# P-MT3620RDB-1-0_PIO.net
KiCad netlist of a schematic drawn in Altium Designer
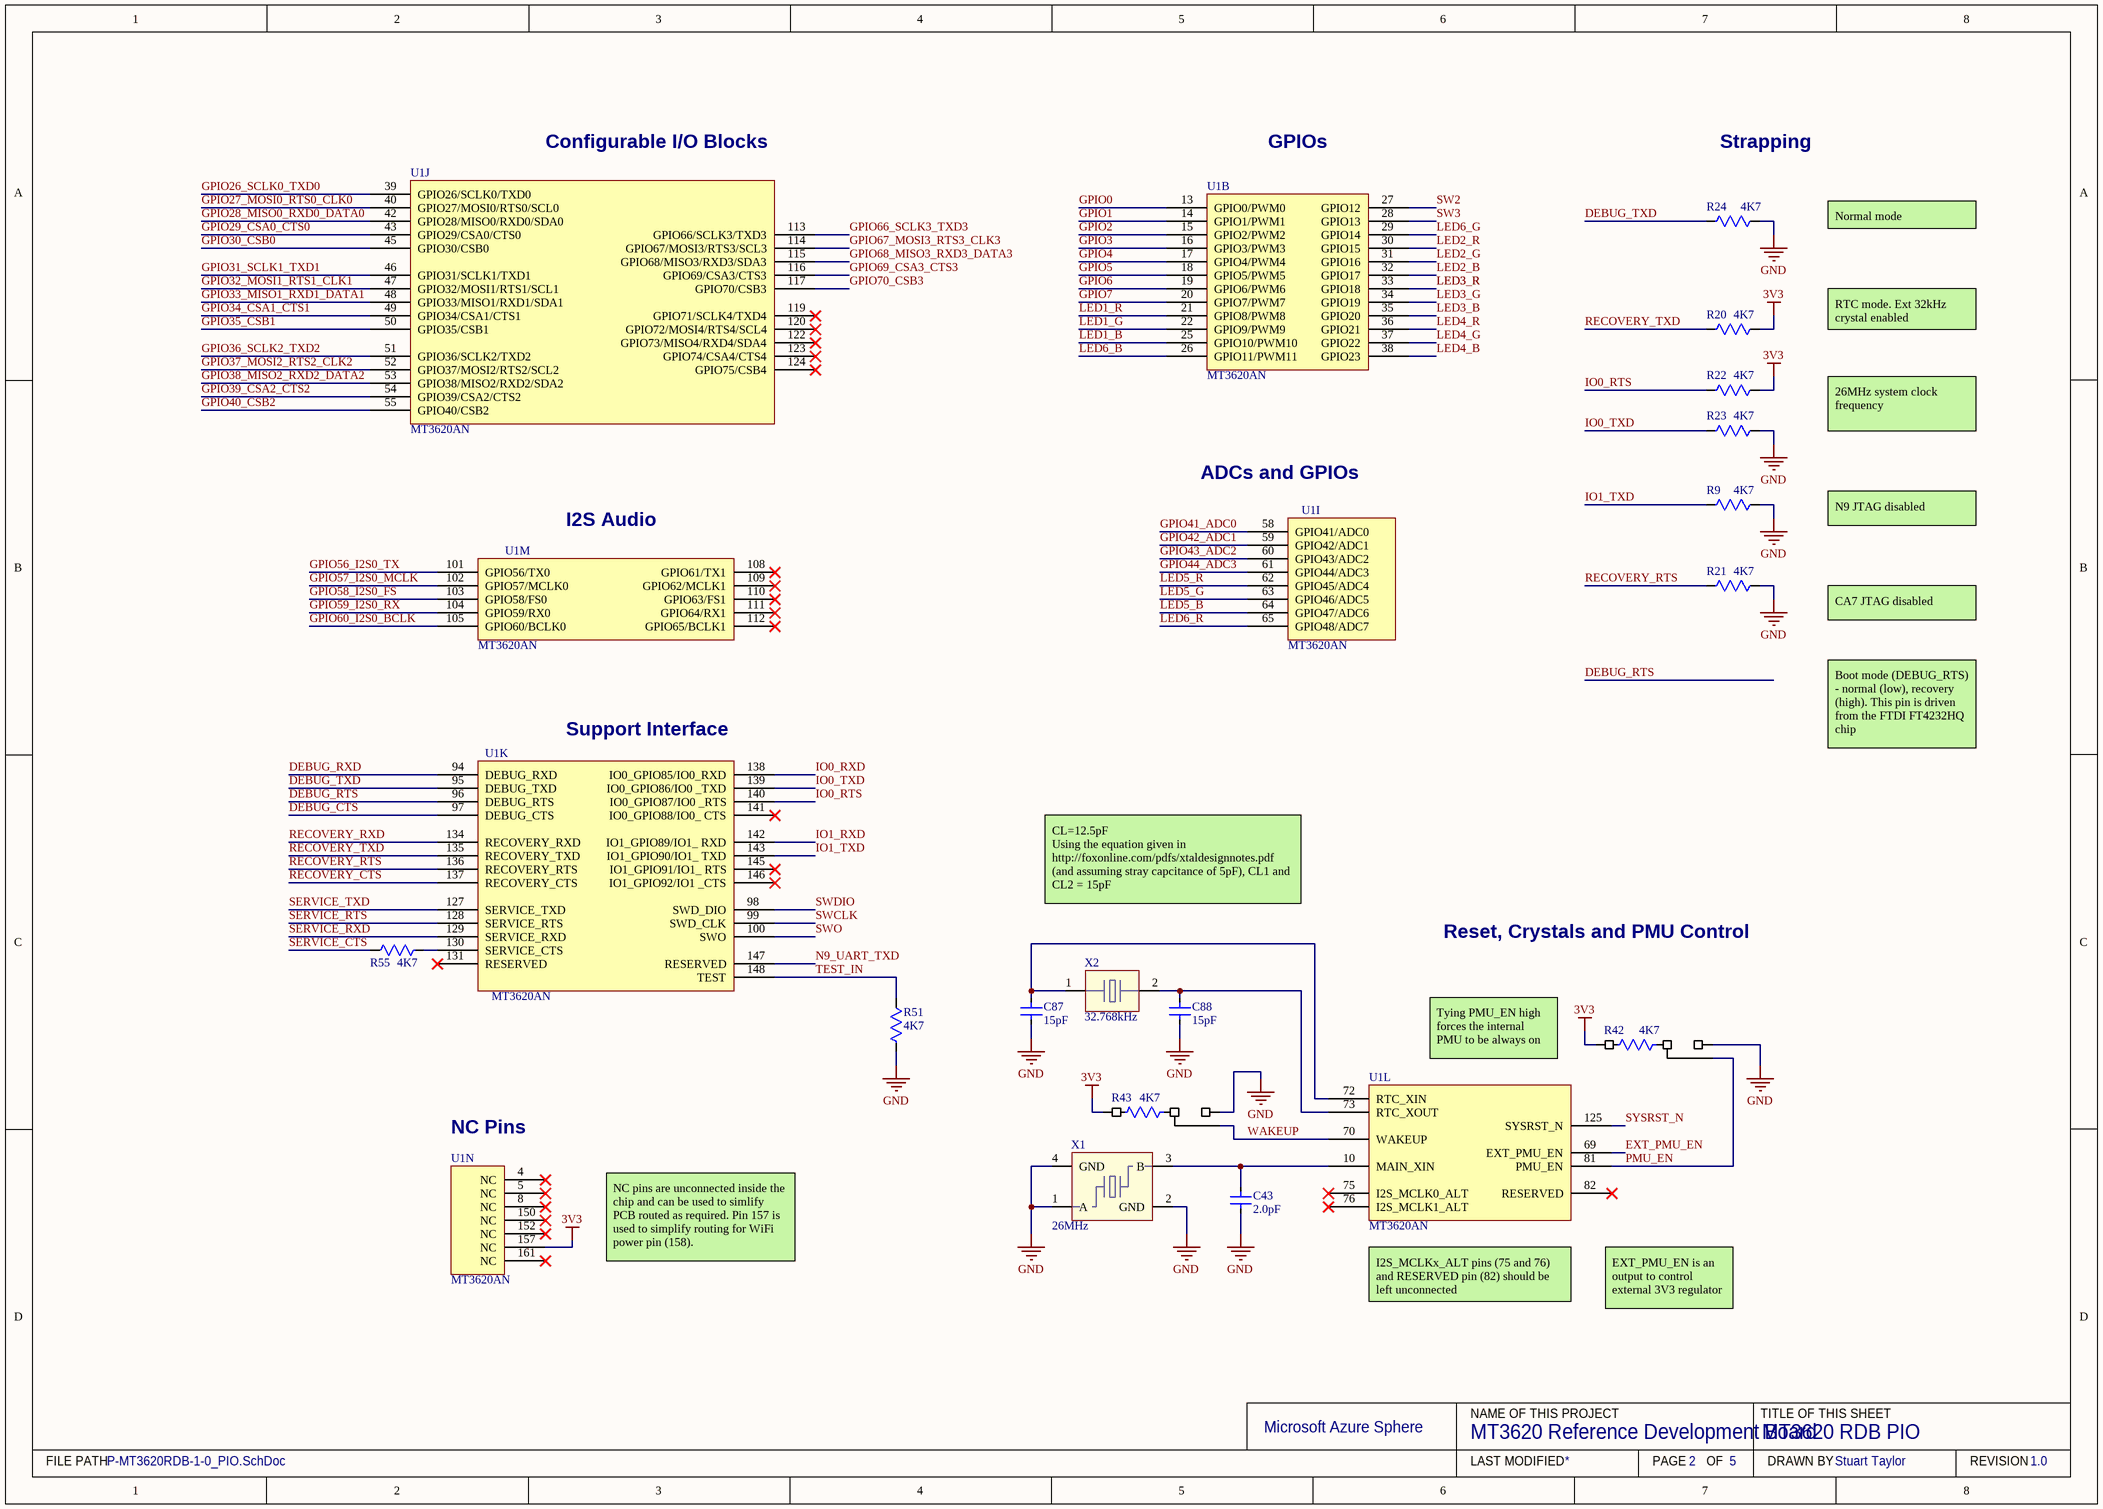
[diagram p0: P-MT3620RDB-1-0_PIO.SchDoc]

(export (version "E")
  (design (tool "Eeschema 10.0.6"))
  (components
    (comp (ref "C43")
      (value "2.0pF")
      (footprint "CAPC1005-EIA0402 0.55MM MED")
      (description "CAP CER 2PF 50V NP0 0402")
      (fields
        (field (name "MANUFACTURER") "TDK Corporation")
        (field (name "MANUFACTURER PART NUMBER") "C1005C0G1H020C050BA")
        (field (name "CAPACITANCE") "2.0pF")
      )
      (libsource (lib "TDK_Capacitor_C_0402") (part "2.0pF 0402 C0G, NP0 50V"))
    )
    (comp (ref "C87")
      (value "15pF")
      (footprint "CAPC1005-EIA0402 0.55MM MED")
      (description "CAP CER 15PF 50V 5% NP0 0402")
      (fields
        (field (name "MANUFACTURER") "TDK Corporation")
        (field (name "MANUFACTURER PART NUMBER") "C1005C0G1H150J050BA")
        (field (name "CAPACITANCE") "15pF")
      )
      (libsource (lib "TDK_Capacitor_C_0402") (part "15pF 0402 C0G, NP0 50V"))
    )
    (comp (ref "C88")
      (value "15pF")
      (footprint "CAPC1005-EIA0402 0.55MM MED")
      (description "CAP CER 15PF 50V 5% NP0 0402")
      (fields
        (field (name "MANUFACTURER") "TDK Corporation")
        (field (name "MANUFACTURER PART NUMBER") "C1005C0G1H150J050BA")
        (field (name "CAPACITANCE") "15pF")
      )
      (libsource (lib "TDK_Capacitor_C_0402") (part "15pF 0402 C0G, NP0 50V"))
    )
    (comp (ref "R9")
      (value "4K7")
      (footprint "RES 0402 MEDIUM DENSITY")
      (description "RES 4.7K OHM 1/10W 1% 0402 SMD")
      (fields
        (field (name "MANUFACTURER") "Panasonic Electronic Components")
        (field (name "MANUFACTURER PART NUMBER") "ERJ-2RKF4701X")
        (field (name "RESISTANCE (OHMS)") "4K7")
      )
      (libsource (lib "Panasonic_Resistor_ERJ2R") (part "4.7K"))
    )
    (comp (ref "R20")
      (value "4K7")
      (footprint "RES 0402 MEDIUM DENSITY")
      (description "RES 4.7K OHM 1/10W 1% 0402 SMD")
      (fields
        (field (name "MANUFACTURER") "Panasonic Electronic Components")
        (field (name "MANUFACTURER PART NUMBER") "ERJ-2RKF4701X")
        (field (name "RESISTANCE (OHMS)") "4K7")
      )
      (libsource (lib "Panasonic_Resistor_ERJ2R") (part "4.7K"))
    )
    (comp (ref "R21")
      (value "4K7")
      (footprint "RES 0402 MEDIUM DENSITY")
      (description "RES 4.7K OHM 1/10W 1% 0402 SMD")
      (fields
        (field (name "MANUFACTURER") "Panasonic Electronic Components")
        (field (name "MANUFACTURER PART NUMBER") "ERJ-2RKF4701X")
        (field (name "RESISTANCE (OHMS)") "4K7")
      )
      (libsource (lib "Panasonic_Resistor_ERJ2R") (part "4.7K"))
    )
    (comp (ref "R22")
      (value "4K7")
      (footprint "RES 0402 MEDIUM DENSITY")
      (description "RES 4.7K OHM 1/10W 1% 0402 SMD")
      (fields
        (field (name "MANUFACTURER") "Panasonic Electronic Components")
        (field (name "MANUFACTURER PART NUMBER") "ERJ-2RKF4701X")
        (field (name "RESISTANCE (OHMS)") "4K7")
      )
      (libsource (lib "Panasonic_Resistor_ERJ2R") (part "4.7K"))
    )
    (comp (ref "R23")
      (value "4K7")
      (footprint "RES 0402 MEDIUM DENSITY")
      (description "RES 4.7K OHM 1/10W 1% 0402 SMD")
      (fields
        (field (name "MANUFACTURER") "Panasonic Electronic Components")
        (field (name "MANUFACTURER PART NUMBER") "ERJ-2RKF4701X")
        (field (name "RESISTANCE (OHMS)") "4K7")
      )
      (libsource (lib "Panasonic_Resistor_ERJ2R") (part "4.7K"))
    )
    (comp (ref "R24")
      (value "4K7")
      (footprint "RES 0402 MEDIUM DENSITY")
      (description "RES 4.7K OHM 1/10W 1% 0402 SMD")
      (fields
        (field (name "MANUFACTURER") "Panasonic Electronic Components")
        (field (name "MANUFACTURER PART NUMBER") "ERJ-2RKF4701X")
        (field (name "RESISTANCE (OHMS)") "4K7")
      )
      (libsource (lib "Panasonic_Resistor_ERJ2R") (part "4.7K"))
    )
    (comp (ref "R42")
      (value "4K7")
      (footprint "THREE-WAY-0402-NO-SHORT")
      (description "RES SMD 4.7K JUMPER 1/10W 0402")
      (fields
        (field (name "MANUFACTURER") "Panasonic Electronic Components")
        (field (name "MANUFACTURER PART NUMBER") "ERJ-2RKF4701X")
      )
      (libsource (lib "generic-res") (part "THREE-WAY-4K7-0402-NO-SHORT"))
    )
    (comp (ref "R43")
      (value "4K7")
      (footprint "THREE-WAY-0402-NO-SHORT")
      (description "RES SMD 4.7K JUMPER 1/10W 0402")
      (fields
        (field (name "MANUFACTURER") "Panasonic Electronic Components")
        (field (name "MANUFACTURER PART NUMBER") "ERJ-2RKF4701X")
      )
      (libsource (lib "generic-res") (part "THREE-WAY-4K7-0402-NO-SHORT"))
    )
    (comp (ref "R51")
      (value "4K7")
      (footprint "RES 0402 MEDIUM DENSITY")
      (description "RES 4.7K OHM 1/10W 1% 0402 SMD")
      (fields
        (field (name "MANUFACTURER") "Panasonic Electronic Components")
        (field (name "MANUFACTURER PART NUMBER") "ERJ-2RKF4701X")
        (field (name "RESISTANCE (OHMS)") "4K7")
      )
      (libsource (lib "Panasonic_Resistor_ERJ2R") (part "4.7K"))
    )
    (comp (ref "R55")
      (value "4K7")
      (footprint "RES 0402 MEDIUM DENSITY")
      (description "RES 4.7K OHM 1/10W 1% 0402 SMD")
      (fields
        (field (name "MANUFACTURER") "Panasonic Electronic Components")
        (field (name "MANUFACTURER PART NUMBER") "ERJ-2RKF4701X")
        (field (name "RESISTANCE (OHMS)") "4K7")
      )
      (libsource (lib "Panasonic_Resistor_ERJ2R") (part "4.7K"))
    )
    (comp (ref "U1")
      (value "MT3620AN")
      (footprint "MT3620_MaskSquaresVias50")
      (fields (field (name "MANUFACTURER") "MediaTek Inc."))
      (libsource (lib "Microsoft") (part "MT3620AN"))
    )
    (comp (ref "X1")
      (value "26MHz")
      (footprint "CT2520DB26000C0FZZA1")
      (description "26MHz crystal")
      (fields
        (field (name "MANUFACTURER") "Siward")
        (field (name "MANUFACTURER PART NUMBER") "XTL581100-M118-0804")
      )
      (libsource (lib "Siward") (part "XTL581100-M118-0804"))
    )
    (comp (ref "X2")
      (value "32.768kHz")
      (footprint "9HT10-32.768KDZF-T")
      (description "32.768kHz ±20ppm Crystal 12.5pF 70 kOhm -40°C ~ 85°C  Surface Mount 2-SMD")
      (fields
        (field (name "MANUFACTURER") "TXC")
        (field (name "MANUFACTURER PART NUMBER") "9HT10-32.768KDZF-T")
      )
      (libsource (lib "TXC") (part "9HT10-32.768KDZF-T"))
    )
  )
  (nets
    (net (code "1") (name "/DEBUG_CTS") (class "Default")
      (node (ref "U1") (pin "97") (pinfunction "DEBUG_CTS_97") (pintype "passive"))
    )
    (net (code "2") (name "/DEBUG_RTS") (class "Default")
      (node (ref "U1") (pin "96") (pinfunction "DEBUG_RTS_96") (pintype "passive"))
    )
    (net (code "3") (name "/DEBUG_RXD") (class "Default")
      (node (ref "U1") (pin "94") (pinfunction "DEBUG_RXD_94") (pintype "passive"))
    )
    (net (code "4") (name "/DEBUG_TXD") (class "Default")
      (node (ref "R24") (pin "2") (pinfunction "2_2") (pintype "passive"))
      (node (ref "U1") (pin "95") (pinfunction "DEBUG_TXD_95") (pintype "passive"))
    )
    (net (code "5") (name "/EXT_PMU_EN") (class "Default")
      (node (ref "U1") (pin "69") (pinfunction "EXT_PMU_EN_69") (pintype "passive"))
    )
    (net (code "6") (name "/GPIO0") (class "Default")
      (node (ref "U1") (pin "13") (pinfunction "GPIO0/PWM0_13") (pintype "passive"))
    )
    (net (code "7") (name "/GPIO1") (class "Default")
      (node (ref "U1") (pin "14") (pinfunction "GPIO1/PWM1_14") (pintype "passive"))
    )
    (net (code "8") (name "/GPIO2") (class "Default")
      (node (ref "U1") (pin "15") (pinfunction "GPIO2/PWM2_15") (pintype "passive"))
    )
    (net (code "9") (name "/GPIO3") (class "Default")
      (node (ref "U1") (pin "16") (pinfunction "GPIO3/PWM3_16") (pintype "passive"))
    )
    (net (code "10") (name "/GPIO4") (class "Default")
      (node (ref "U1") (pin "17") (pinfunction "GPIO4/PWM4_17") (pintype "passive"))
    )
    (net (code "11") (name "/GPIO5") (class "Default")
      (node (ref "U1") (pin "18") (pinfunction "GPIO5/PWM5_18") (pintype "passive"))
    )
    (net (code "12") (name "/GPIO6") (class "Default")
      (node (ref "U1") (pin "19") (pinfunction "GPIO6/PWM6_19") (pintype "passive"))
    )
    (net (code "13") (name "/GPIO7") (class "Default")
      (node (ref "U1") (pin "20") (pinfunction "GPIO7/PWM7_20") (pintype "passive"))
    )
    (net (code "14") (name "/GPIO26_SCLK0_TXD0") (class "Default")
      (node (ref "U1") (pin "39") (pinfunction "GPIO26/SCLK0/TXD0_39") (pintype "passive"))
    )
    (net (code "15") (name "/GPIO27_MOSI0_RTS0_CLK0") (class "Default")
      (node (ref "U1") (pin "40") (pinfunction "GPIO27/MOSI0/RTS0/SCL0_40") (pintype "passive"))
    )
    (net (code "16") (name "/GPIO28_MISO0_RXD0_DATA0") (class "Default")
      (node (ref "U1") (pin "42") (pinfunction "GPIO28/MISO0/RXD0/SDA0_42") (pintype "passive"))
    )
    (net (code "17") (name "/GPIO29_CSA0_CTS0") (class "Default")
      (node (ref "U1") (pin "43") (pinfunction "GPIO29/CSA0/CTS0_43") (pintype "passive"))
    )
    (net (code "18") (name "/GPIO30_CSB0") (class "Default")
      (node (ref "U1") (pin "45") (pinfunction "GPIO30/CSB0_45") (pintype "passive"))
    )
    (net (code "19") (name "/GPIO31_SCLK1_TXD1") (class "Default")
      (node (ref "U1") (pin "46") (pinfunction "GPIO31/SCLK1/TXD1_46") (pintype "passive"))
    )
    (net (code "20") (name "/GPIO32_MOSI1_RTS1_CLK1") (class "Default")
      (node (ref "U1") (pin "47") (pinfunction "GPIO32/MOSI1/RTS1/SCL1_47") (pintype "passive"))
    )
    (net (code "21") (name "/GPIO33_MISO1_RXD1_DATA1") (class "Default")
      (node (ref "U1") (pin "48") (pinfunction "GPIO33/MISO1/RXD1/SDA1_48") (pintype "passive"))
    )
    (net (code "22") (name "/GPIO34_CSA1_CTS1") (class "Default")
      (node (ref "U1") (pin "49") (pinfunction "GPIO34/CSA1/CTS1_49") (pintype "passive"))
    )
    (net (code "23") (name "/GPIO35_CSB1") (class "Default")
      (node (ref "U1") (pin "50") (pinfunction "GPIO35/CSB1_50") (pintype "passive"))
    )
    (net (code "24") (name "/GPIO36_SCLK2_TXD2") (class "Default")
      (node (ref "U1") (pin "51") (pinfunction "GPIO36/SCLK2/TXD2_51") (pintype "passive"))
    )
    (net (code "25") (name "/GPIO37_MOSI2_RTS2_CLK2") (class "Default")
      (node (ref "U1") (pin "52") (pinfunction "GPIO37/MOSI2/RTS2/SCL2_52") (pintype "passive"))
    )
    (net (code "26") (name "/GPIO38_MISO2_RXD2_DATA2") (class "Default")
      (node (ref "U1") (pin "53") (pinfunction "GPIO38/MISO2/RXD2/SDA2_53") (pintype "passive"))
    )
    (net (code "27") (name "/GPIO39_CSA2_CTS2") (class "Default")
      (node (ref "U1") (pin "54") (pinfunction "GPIO39/CSA2/CTS2_54") (pintype "passive"))
    )
    (net (code "28") (name "/GPIO40_CSB2") (class "Default")
      (node (ref "U1") (pin "55") (pinfunction "GPIO40/CSB2_55") (pintype "passive"))
    )
    (net (code "29") (name "/GPIO41_ADC0") (class "Default")
      (node (ref "U1") (pin "58") (pinfunction "GPIO41/ADC0_58") (pintype "passive"))
    )
    (net (code "30") (name "/GPIO42_ADC1") (class "Default")
      (node (ref "U1") (pin "59") (pinfunction "GPIO42/ADC1_59") (pintype "passive"))
    )
    (net (code "31") (name "/GPIO43_ADC2") (class "Default")
      (node (ref "U1") (pin "60") (pinfunction "GPIO43/ADC2_60") (pintype "passive"))
    )
    (net (code "32") (name "/GPIO44_ADC3") (class "Default")
      (node (ref "U1") (pin "61") (pinfunction "GPIO44/ADC3_61") (pintype "passive"))
    )
    (net (code "33") (name "/GPIO56_I2S0_TX") (class "Default")
      (node (ref "U1") (pin "101") (pinfunction "GPIO56/TX0_101") (pintype "passive"))
    )
    (net (code "34") (name "/GPIO57_I2S0_MCLK") (class "Default")
      (node (ref "U1") (pin "102") (pinfunction "GPIO57/MCLK0_102") (pintype "passive"))
    )
    (net (code "35") (name "/GPIO58_I2S0_FS") (class "Default")
      (node (ref "U1") (pin "103") (pinfunction "GPIO58/FS0_103") (pintype "passive"))
    )
    (net (code "36") (name "/GPIO59_I2S0_RX") (class "Default")
      (node (ref "U1") (pin "104") (pinfunction "GPIO59/RX0_104") (pintype "passive"))
    )
    (net (code "37") (name "/GPIO60_I2S0_BCLK") (class "Default")
      (node (ref "U1") (pin "105") (pinfunction "GPIO60/BCLK0_105") (pintype "passive"))
    )
    (net (code "38") (name "/GPIO66_SCLK3_TXD3") (class "Default")
      (node (ref "U1") (pin "113") (pinfunction "GPIO66/SCLK3/TXD3_113") (pintype "passive"))
    )
    (net (code "39") (name "/GPIO67_MOSI3_RTS3_CLK3") (class "Default")
      (node (ref "U1") (pin "114") (pinfunction "GPIO67/MOSI3/RTS3/SCL3_114") (pintype "passive"))
    )
    (net (code "40") (name "/GPIO68_MISO3_RXD3_DATA3") (class "Default")
      (node (ref "U1") (pin "115") (pinfunction "GPIO68/MISO3/RXD3/SDA3_115") (pintype "passive"))
    )
    (net (code "41") (name "/GPIO69_CSA3_CTS3") (class "Default")
      (node (ref "U1") (pin "116") (pinfunction "GPIO69/CSA3/CTS3_116") (pintype "passive"))
    )
    (net (code "42") (name "/GPIO70_CSB3") (class "Default")
      (node (ref "U1") (pin "117") (pinfunction "GPIO70/CSB3_117") (pintype "passive"))
    )
    (net (code "43") (name "/IO0_RTS") (class "Default")
      (node (ref "R22") (pin "2") (pinfunction "2_2") (pintype "passive"))
      (node (ref "U1") (pin "140") (pinfunction "IO0_GPIO87/IO0__RTS_140") (pintype "passive"))
    )
    (net (code "44") (name "/IO0_RXD") (class "Default")
      (node (ref "U1") (pin "138") (pinfunction "IO0_GPIO85/IO0_RXD_138") (pintype "passive"))
    )
    (net (code "45") (name "/IO0_TXD") (class "Default")
      (node (ref "R23") (pin "2") (pinfunction "2_2") (pintype "passive"))
      (node (ref "U1") (pin "139") (pinfunction "IO0_GPIO86/IO0__TXD_139") (pintype "passive"))
    )
    (net (code "46") (name "/IO1_RXD") (class "Default")
      (node (ref "U1") (pin "142") (pinfunction "IO1_GPIO89/IO1__RXD_142") (pintype "passive"))
    )
    (net (code "47") (name "/IO1_TXD") (class "Default")
      (node (ref "R9") (pin "2") (pinfunction "2_2") (pintype "passive"))
      (node (ref "U1") (pin "143") (pinfunction "IO1_GPIO90/IO1__TXD_143") (pintype "passive"))
    )
    (net (code "48") (name "/LED1_B") (class "Default")
      (node (ref "U1") (pin "25") (pinfunction "GPIO10/PWM10_25") (pintype "passive"))
    )
    (net (code "49") (name "/LED1_G") (class "Default")
      (node (ref "U1") (pin "22") (pinfunction "GPIO9/PWM9_22") (pintype "passive"))
    )
    (net (code "50") (name "/LED1_R") (class "Default")
      (node (ref "U1") (pin "21") (pinfunction "GPIO8/PWM8_21") (pintype "passive"))
    )
    (net (code "51") (name "/LED2_B") (class "Default")
      (node (ref "U1") (pin "32") (pinfunction "GPIO17_32") (pintype "passive"))
    )
    (net (code "52") (name "/LED2_G") (class "Default")
      (node (ref "U1") (pin "31") (pinfunction "GPIO16_31") (pintype "passive"))
    )
    (net (code "53") (name "/LED2_R") (class "Default")
      (node (ref "U1") (pin "30") (pinfunction "GPIO15_30") (pintype "passive"))
    )
    (net (code "54") (name "/LED3_B") (class "Default")
      (node (ref "U1") (pin "35") (pinfunction "GPIO20_35") (pintype "passive"))
    )
    (net (code "55") (name "/LED3_G") (class "Default")
      (node (ref "U1") (pin "34") (pinfunction "GPIO19_34") (pintype "passive"))
    )
    (net (code "56") (name "/LED3_R") (class "Default")
      (node (ref "U1") (pin "33") (pinfunction "GPIO18_33") (pintype "passive"))
    )
    (net (code "57") (name "/LED4_B") (class "Default")
      (node (ref "U1") (pin "38") (pinfunction "GPIO23_38") (pintype "passive"))
    )
    (net (code "58") (name "/LED4_G") (class "Default")
      (node (ref "U1") (pin "37") (pinfunction "GPIO22_37") (pintype "passive"))
    )
    (net (code "59") (name "/LED4_R") (class "Default")
      (node (ref "U1") (pin "36") (pinfunction "GPIO21_36") (pintype "passive"))
    )
    (net (code "60") (name "/LED5_B") (class "Default")
      (node (ref "U1") (pin "64") (pinfunction "GPIO47/ADC6_64") (pintype "passive"))
    )
    (net (code "61") (name "/LED5_G") (class "Default")
      (node (ref "U1") (pin "63") (pinfunction "GPIO46/ADC5_63") (pintype "passive"))
    )
    (net (code "62") (name "/LED5_R") (class "Default")
      (node (ref "U1") (pin "62") (pinfunction "GPIO45/ADC4_62") (pintype "passive"))
    )
    (net (code "63") (name "/LED6_B") (class "Default")
      (node (ref "U1") (pin "26") (pinfunction "GPIO11/PWM11_26") (pintype "passive"))
    )
    (net (code "64") (name "/LED6_G") (class "Default")
      (node (ref "U1") (pin "29") (pinfunction "GPIO14_29") (pintype "passive"))
    )
    (net (code "65") (name "/LED6_R") (class "Default")
      (node (ref "U1") (pin "65") (pinfunction "GPIO48/ADC7_65") (pintype "passive"))
    )
    (net (code "66") (name "/N9_UART_TXD") (class "Default")
      (node (ref "U1") (pin "147") (pinfunction "RESERVED_147") (pintype "passive"))
    )
    (net (code "67") (name "/PMU_EN") (class "Default")
      (node (ref "R42") (pin "2") (pinfunction "2_2") (pintype "passive"))
      (node (ref "U1") (pin "81") (pinfunction "PMU_EN_81") (pintype "passive"))
    )
    (net (code "68") (name "/RECOVERY_CTS") (class "Default")
      (node (ref "U1") (pin "137") (pinfunction "RECOVERY_CTS_137") (pintype "passive"))
    )
    (net (code "69") (name "/RECOVERY_RTS") (class "Default")
      (node (ref "R21") (pin "2") (pinfunction "2_2") (pintype "passive"))
      (node (ref "U1") (pin "136") (pinfunction "RECOVERY_RTS_136") (pintype "passive"))
    )
    (net (code "70") (name "/RECOVERY_RXD") (class "Default")
      (node (ref "U1") (pin "134") (pinfunction "RECOVERY_RXD_134") (pintype "passive"))
    )
    (net (code "71") (name "/RECOVERY_TXD") (class "Default")
      (node (ref "R20") (pin "2") (pinfunction "2_2") (pintype "passive"))
      (node (ref "U1") (pin "135") (pinfunction "RECOVERY_TXD_135") (pintype "passive"))
    )
    (net (code "72") (name "/SERVICE_CTS") (class "Default")
      (node (ref "R55") (pin "1") (pinfunction "1_1") (pintype "passive"))
    )
    (net (code "73") (name "/SERVICE_RTS") (class "Default")
      (node (ref "U1") (pin "128") (pinfunction "SERVICE_RTS_128") (pintype "passive"))
    )
    (net (code "74") (name "/SERVICE_RXD") (class "Default")
      (node (ref "U1") (pin "129") (pinfunction "SERVICE_RXD_129") (pintype "passive"))
    )
    (net (code "75") (name "/SERVICE_TXD") (class "Default")
      (node (ref "U1") (pin "127") (pinfunction "SERVICE_TXD_127") (pintype "passive"))
    )
    (net (code "76") (name "/SW2") (class "Default")
      (node (ref "U1") (pin "27") (pinfunction "GPIO12_27") (pintype "passive"))
    )
    (net (code "77") (name "/SW3") (class "Default")
      (node (ref "U1") (pin "28") (pinfunction "GPIO13_28") (pintype "passive"))
    )
    (net (code "78") (name "/SWCLK") (class "Default")
      (node (ref "U1") (pin "99") (pinfunction "SWD_CLK_99") (pintype "passive"))
    )
    (net (code "79") (name "/SWDIO") (class "Default")
      (node (ref "U1") (pin "98") (pinfunction "SWD_DIO_98") (pintype "passive"))
    )
    (net (code "80") (name "/SWO") (class "Default")
      (node (ref "U1") (pin "100") (pinfunction "SWO_100") (pintype "passive"))
    )
    (net (code "81") (name "/SYSRST_N") (class "Default")
      (node (ref "U1") (pin "125") (pinfunction "SYSRST_N_125") (pintype "passive"))
    )
    (net (code "82") (name "/TEST_IN") (class "Default")
      (node (ref "R51") (pin "1") (pinfunction "1_1") (pintype "passive"))
      (node (ref "U1") (pin "148") (pinfunction "TEST_148") (pintype "passive"))
    )
    (net (code "83") (name "/WAKEUP") (class "Default")
      (node (ref "R43") (pin "2") (pinfunction "2_2") (pintype "passive"))
      (node (ref "U1") (pin "70") (pinfunction "WAKEUP_70") (pintype "passive"))
    )
    (net (code "84") (name "3V3") (class "Default")
      (node (ref "R20") (pin "1") (pinfunction "1_1") (pintype "passive"))
      (node (ref "R22") (pin "1") (pinfunction "1_1") (pintype "passive"))
      (node (ref "R42") (pin "1") (pinfunction "1_1") (pintype "passive"))
      (node (ref "R43") (pin "1") (pinfunction "1_1") (pintype "passive"))
      (node (ref "U1") (pin "157") (pinfunction "NC_157") (pintype "passive"))
    )
    (net (code "85") (name "GND") (class "Default")
      (node (ref "C43") (pin "1") (pinfunction "1_1") (pintype "passive"))
      (node (ref "C87") (pin "1") (pinfunction "1_1") (pintype "passive"))
      (node (ref "C88") (pin "1") (pinfunction "1_1") (pintype "passive"))
      (node (ref "R21") (pin "1") (pinfunction "1_1") (pintype "passive"))
      (node (ref "R23") (pin "1") (pinfunction "1_1") (pintype "passive"))
      (node (ref "R24") (pin "1") (pinfunction "1_1") (pintype "passive"))
      (node (ref "R42") (pin "3") (pinfunction "3_3") (pintype "passive"))
      (node (ref "R43") (pin "3") (pinfunction "3_3") (pintype "passive"))
      (node (ref "R51") (pin "2") (pinfunction "2_2") (pintype "passive"))
      (node (ref "R9") (pin "1") (pinfunction "1_1") (pintype "passive"))
      (node (ref "X1") (pin "1") (pinfunction "A_1") (pintype "passive"))
      (node (ref "X1") (pin "2") (pinfunction "GND_2") (pintype "passive"))
      (node (ref "X1") (pin "4") (pinfunction "GND_4") (pintype "passive"))
    )
    (net (code "86") (name "Net-(U1K-SERVICE_CTS)") (class "Default")
      (node (ref "R55") (pin "2") (pinfunction "2_2") (pintype "passive"))
      (node (ref "U1") (pin "130") (pinfunction "SERVICE_CTS_130") (pintype "passive"))
    )
    (net (code "87") (name "Net-(U1L-MAIN_XIN)") (class "Default")
      (node (ref "C43") (pin "2") (pinfunction "2_2") (pintype "passive"))
      (node (ref "U1") (pin "10") (pinfunction "MAIN_XIN_10") (pintype "passive"))
      (node (ref "X1") (pin "3") (pinfunction "B_3") (pintype "passive"))
    )
    (net (code "88") (name "Net-(U1L-RTC_XIN)") (class "Default")
      (node (ref "C87") (pin "2") (pinfunction "2_2") (pintype "passive"))
      (node (ref "U1") (pin "72") (pinfunction "RTC_XIN_72") (pintype "passive"))
      (node (ref "X2") (pin "1") (pinfunction "1_1") (pintype "passive"))
    )
    (net (code "89") (name "Net-(U1L-RTC_XOUT)") (class "Default")
      (node (ref "C88") (pin "2") (pinfunction "2_2") (pintype "passive"))
      (node (ref "U1") (pin "73") (pinfunction "RTC_XOUT_73") (pintype "passive"))
      (node (ref "X2") (pin "2") (pinfunction "2_2") (pintype "passive"))
    )
    (net (code "90") (name "unconnected-(U1J-GPIO71{slash}SCLK4{slash}TXD4-Pad119)") (class "Default")
      (node (ref "U1") (pin "119") (pinfunction "GPIO71/SCLK4/TXD4_119") (pintype "passive+no_connect"))
    )
    (net (code "91") (name "unconnected-(U1J-GPIO72{slash}MOSI4{slash}RTS4{slash}SCL4-Pad120)") (class "Default")
      (node (ref "U1") (pin "120") (pinfunction "GPIO72/MOSI4/RTS4/SCL4_120") (pintype "passive+no_connect"))
    )
    (net (code "92") (name "unconnected-(U1J-GPIO73{slash}MISO4{slash}RXD4{slash}SDA4-Pad122)") (class "Default")
      (node (ref "U1") (pin "122") (pinfunction "GPIO73/MISO4/RXD4/SDA4_122") (pintype "passive+no_connect"))
    )
    (net (code "93") (name "unconnected-(U1J-GPIO74{slash}CSA4{slash}CTS4-Pad123)") (class "Default")
      (node (ref "U1") (pin "123") (pinfunction "GPIO74/CSA4/CTS4_123") (pintype "passive+no_connect"))
    )
    (net (code "94") (name "unconnected-(U1J-GPIO75{slash}CSB4-Pad124)") (class "Default")
      (node (ref "U1") (pin "124") (pinfunction "GPIO75/CSB4_124") (pintype "passive+no_connect"))
    )
    (net (code "95") (name "unconnected-(U1K-IO0_GPIO88{slash}IO0__CTS-Pad141)") (class "Default")
      (node (ref "U1") (pin "141") (pinfunction "IO0_GPIO88/IO0__CTS_141") (pintype "passive+no_connect"))
    )
    (net (code "96") (name "unconnected-(U1K-IO1_GPIO91{slash}IO1__RTS-Pad145)") (class "Default")
      (node (ref "U1") (pin "145") (pinfunction "IO1_GPIO91/IO1__RTS_145") (pintype "passive+no_connect"))
    )
    (net (code "97") (name "unconnected-(U1K-IO1_GPIO92{slash}IO1__CTS-Pad146)") (class "Default")
      (node (ref "U1") (pin "146") (pinfunction "IO1_GPIO92/IO1__CTS_146") (pintype "passive+no_connect"))
    )
    (net (code "98") (name "unconnected-(U1K-RESERVED-Pad131)") (class "Default")
      (node (ref "U1") (pin "131") (pinfunction "RESERVED_131") (pintype "passive+no_connect"))
    )
    (net (code "99") (name "unconnected-(U1L-I2S_MCLK0_ALT-Pad75)") (class "Default")
      (node (ref "U1") (pin "75") (pinfunction "I2S_MCLK0_ALT_75") (pintype "passive+no_connect"))
    )
    (net (code "100") (name "unconnected-(U1L-I2S_MCLK1_ALT-Pad76)") (class "Default")
      (node (ref "U1") (pin "76") (pinfunction "I2S_MCLK1_ALT_76") (pintype "passive+no_connect"))
    )
    (net (code "101") (name "unconnected-(U1L-RESERVED-Pad82)") (class "Default")
      (node (ref "U1") (pin "82") (pinfunction "RESERVED_82") (pintype "passive+no_connect"))
    )
    (net (code "102") (name "unconnected-(U1M-GPIO61{slash}TX1-Pad108)") (class "Default")
      (node (ref "U1") (pin "108") (pinfunction "GPIO61/TX1_108") (pintype "passive+no_connect"))
    )
    (net (code "103") (name "unconnected-(U1M-GPIO62{slash}MCLK1-Pad109)") (class "Default")
      (node (ref "U1") (pin "109") (pinfunction "GPIO62/MCLK1_109") (pintype "passive+no_connect"))
    )
    (net (code "104") (name "unconnected-(U1M-GPIO63{slash}FS1-Pad110)") (class "Default")
      (node (ref "U1") (pin "110") (pinfunction "GPIO63/FS1_110") (pintype "passive+no_connect"))
    )
    (net (code "105") (name "unconnected-(U1M-GPIO64{slash}RX1-Pad111)") (class "Default")
      (node (ref "U1") (pin "111") (pinfunction "GPIO64/RX1_111") (pintype "passive+no_connect"))
    )
    (net (code "106") (name "unconnected-(U1M-GPIO65{slash}BCLK1-Pad112)") (class "Default")
      (node (ref "U1") (pin "112") (pinfunction "GPIO65/BCLK1_112") (pintype "passive+no_connect"))
    )
    (net (code "107") (name "unconnected-(U1N-NC-Pad4)") (class "Default")
      (node (ref "U1") (pin "4") (pinfunction "NC_4") (pintype "passive+no_connect"))
    )
    (net (code "108") (name "unconnected-(U1N-NC-Pad5)") (class "Default")
      (node (ref "U1") (pin "5") (pinfunction "NC_5") (pintype "passive+no_connect"))
    )
    (net (code "109") (name "unconnected-(U1N-NC-Pad8)") (class "Default")
      (node (ref "U1") (pin "8") (pinfunction "NC_8") (pintype "passive+no_connect"))
    )
    (net (code "110") (name "unconnected-(U1N-NC-Pad150)") (class "Default")
      (node (ref "U1") (pin "150") (pinfunction "NC_150") (pintype "passive+no_connect"))
    )
    (net (code "111") (name "unconnected-(U1N-NC-Pad152)") (class "Default")
      (node (ref "U1") (pin "152") (pinfunction "NC_152") (pintype "passive+no_connect"))
    )
    (net (code "112") (name "unconnected-(U1N-NC-Pad161)") (class "Default")
      (node (ref "U1") (pin "161") (pinfunction "NC_161") (pintype "passive+no_connect"))
    )
  )
)
